# Osillatore_Variabile_Intonazione.net
KiCad netlist of a schematic drawn in EAGLE
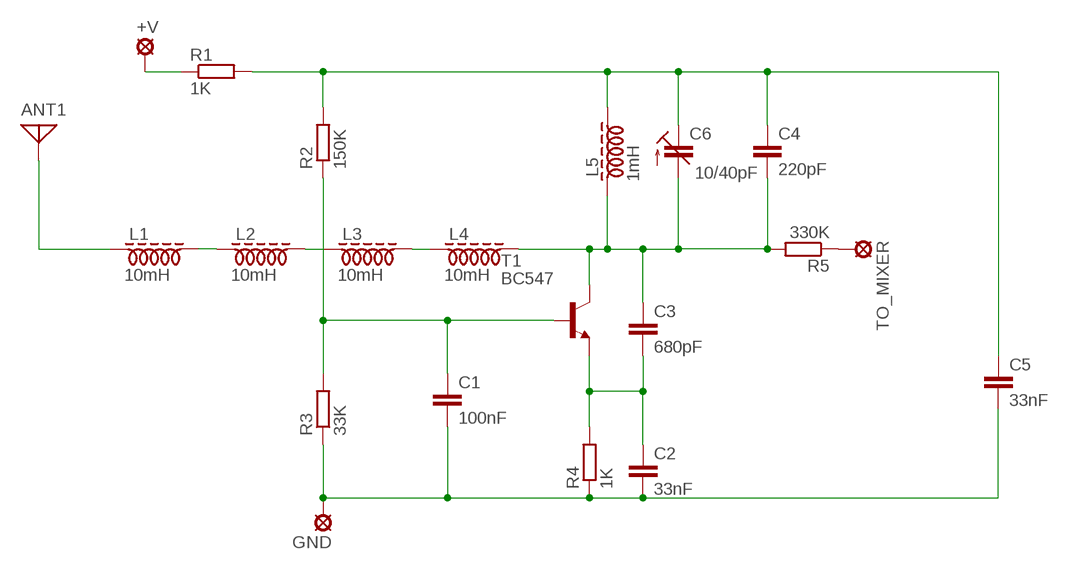
[diagram p0: schematic, sheet 1]

(export (version "E")
  (design (tool "Eeschema 10.0.6"))
  (components
    (comp (ref "+V")
      (value "LSP10")
      (footprint "eagle-import:LSP10")
      (libsource (lib "eagle-import") (part "LSP10"))
    )
    (comp (ref "ANT1")
      (value "ANTENNA")
      (footprint "eagle-import:PAD-01")
      (libsource (lib "eagle-import") (part "ANTENNA"))
    )
    (comp (ref "C1")
      (value "100nF")
      (footprint "eagle-import:C025-060X050")
      (libsource (lib "eagle-import") (part "C-EU025-060X050"))
    )
    (comp (ref "C2")
      (value "33nF")
      (footprint "eagle-import:C025-060X050")
      (libsource (lib "eagle-import") (part "C-EU025-060X050"))
    )
    (comp (ref "C3")
      (value "680pF")
      (footprint "eagle-import:C025-060X050")
      (libsource (lib "eagle-import") (part "C-EU025-060X050"))
    )
    (comp (ref "C4")
      (value "220pF")
      (footprint "eagle-import:C025-060X050")
      (libsource (lib "eagle-import") (part "C-EU025-060X050"))
    )
    (comp (ref "C5")
      (value "33nF")
      (footprint "eagle-import:C025-060X050")
      (libsource (lib "eagle-import") (part "C-EU025-060X050"))
    )
    (comp (ref "C6")
      (value "10/40pF")
      (footprint "eagle-import:3008")
      (libsource (lib "eagle-import") (part "C-TRIMM3008"))
    )
    (comp (ref "GND")
      (value "LSP10")
      (footprint "eagle-import:LSP10")
      (libsource (lib "eagle-import") (part "LSP10"))
    )
    (comp (ref "L1")
      (value "10mH")
      (footprint "eagle-import:Z28_7")
      (libsource (lib "eagle-import") (part "Z?CW28/70"))
    )
    (comp (ref "L2")
      (value "10mH")
      (footprint "eagle-import:Z28_7")
      (libsource (lib "eagle-import") (part "Z?CW28/70"))
    )
    (comp (ref "L3")
      (value "10mH")
      (footprint "eagle-import:Z28_7")
      (libsource (lib "eagle-import") (part "Z?CW28/70"))
    )
    (comp (ref "L4")
      (value "10mH")
      (footprint "eagle-import:Z28_7")
      (libsource (lib "eagle-import") (part "Z?CW28/70"))
    )
    (comp (ref "L5")
      (value "1mH")
      (footprint "eagle-import:Z28_7")
      (libsource (lib "eagle-import") (part "Z?CW28/70"))
    )
    (comp (ref "R1")
      (value "1K")
      (footprint "eagle-import:0207_7")
      (libsource (lib "eagle-import") (part "R-EU_0207/7"))
    )
    (comp (ref "R2")
      (value "150K")
      (footprint "eagle-import:0207_7")
      (libsource (lib "eagle-import") (part "R-EU_0207/7"))
    )
    (comp (ref "R3")
      (value "33K")
      (footprint "eagle-import:0207_7")
      (libsource (lib "eagle-import") (part "R-EU_0207/7"))
    )
    (comp (ref "R4")
      (value "1K")
      (footprint "eagle-import:0207_7")
      (libsource (lib "eagle-import") (part "R-EU_0207/7"))
    )
    (comp (ref "R5")
      (value "330K")
      (footprint "eagle-import:0207_7")
      (libsource (lib "eagle-import") (part "R-EU_0207/7"))
    )
    (comp (ref "T1")
      (value "BC547")
      (footprint "eagle-import:TO92")
      (libsource (lib "eagle-import") (part "BC547"))
    )
    (comp (ref "TO_MIXER")
      (value "LSP10")
      (footprint "eagle-import:LSP10")
      (libsource (lib "eagle-import") (part "LSP10"))
    )
  )
  (nets
    (net (code "1") (name "Net-(+V-PadMP)") (class "Default")
      (node (ref "+V") (pin "MP") (pinfunction "MP_MP") (pintype "passive"))
      (node (ref "R1") (pin "1") (pinfunction "1_1") (pintype "passive"))
    )
    (net (code "2") (name "Net-(ANT1-Pad1)") (class "Default")
      (node (ref "ANT1") (pin "1") (pinfunction "1_1") (pintype "output"))
      (node (ref "L1") (pin "1") (pinfunction "1_1") (pintype "passive"))
    )
    (net (code "3") (name "Net-(C1-Pad2)") (class "Default")
      (node (ref "C1") (pin "2") (pinfunction "2_2") (pintype "passive"))
      (node (ref "C2") (pin "2") (pinfunction "2_2") (pintype "passive"))
      (node (ref "C5") (pin "2") (pinfunction "2_2") (pintype "passive"))
      (node (ref "GND") (pin "MP") (pinfunction "MP_MP") (pintype "passive"))
      (node (ref "R3") (pin "1") (pinfunction "1_1") (pintype "passive"))
      (node (ref "R4") (pin "1") (pinfunction "1_1") (pintype "passive"))
    )
    (net (code "4") (name "Net-(C6-A)") (class "Default")
      (node (ref "C3") (pin "1") (pinfunction "1_1") (pintype "passive"))
      (node (ref "C4") (pin "2") (pinfunction "2_2") (pintype "passive"))
      (node (ref "C6") (pin "-") (pinfunction "A_-") (pintype "passive"))
      (node (ref "L4") (pin "2") (pinfunction "2_2") (pintype "passive"))
      (node (ref "L5") (pin "1") (pinfunction "1_1") (pintype "passive"))
      (node (ref "R5") (pin "2") (pinfunction "2_2") (pintype "passive"))
      (node (ref "T1") (pin "3") (pinfunction "C_3") (pintype "passive"))
    )
    (net (code "5") (name "Net-(C6-E)") (class "Default")
      (node (ref "C4") (pin "1") (pinfunction "1_1") (pintype "passive"))
      (node (ref "C5") (pin "1") (pinfunction "1_1") (pintype "passive"))
      (node (ref "C6") (pin "+") (pinfunction "E_+") (pintype "passive"))
      (node (ref "L5") (pin "2") (pinfunction "2_2") (pintype "passive"))
      (node (ref "R1") (pin "2") (pinfunction "2_2") (pintype "passive"))
      (node (ref "R2") (pin "2") (pinfunction "2_2") (pintype "passive"))
    )
    (net (code "6") (name "Net-(L1-Pad2)") (class "Default")
      (node (ref "L1") (pin "2") (pinfunction "2_2") (pintype "passive"))
      (node (ref "L2") (pin "1") (pinfunction "1_1") (pintype "passive"))
    )
    (net (code "7") (name "Net-(L2-Pad2)") (class "Default")
      (node (ref "L2") (pin "2") (pinfunction "2_2") (pintype "passive"))
      (node (ref "L3") (pin "1") (pinfunction "1_1") (pintype "passive"))
    )
    (net (code "8") (name "Net-(L3-Pad2)") (class "Default")
      (node (ref "L3") (pin "2") (pinfunction "2_2") (pintype "passive"))
      (node (ref "L4") (pin "1") (pinfunction "1_1") (pintype "passive"))
    )
    (net (code "9") (name "Net-(R5-Pad1)") (class "Default")
      (node (ref "R5") (pin "1") (pinfunction "1_1") (pintype "passive"))
      (node (ref "TO_MIXER") (pin "MP") (pinfunction "MP_MP") (pintype "passive"))
    )
    (net (code "10") (name "Net-(T1-B)") (class "Default")
      (node (ref "C1") (pin "1") (pinfunction "1_1") (pintype "passive"))
      (node (ref "R2") (pin "1") (pinfunction "1_1") (pintype "passive"))
      (node (ref "R3") (pin "2") (pinfunction "2_2") (pintype "passive"))
      (node (ref "T1") (pin "2") (pinfunction "B_2") (pintype "passive"))
    )
    (net (code "11") (name "Net-(T1-E)") (class "Default")
      (node (ref "C2") (pin "1") (pinfunction "1_1") (pintype "passive"))
      (node (ref "C3") (pin "2") (pinfunction "2_2") (pintype "passive"))
      (node (ref "R4") (pin "2") (pinfunction "2_2") (pintype "passive"))
      (node (ref "T1") (pin "1") (pinfunction "E_1") (pintype "passive"))
    )
  )
)
